# ring-modulator-v2_0.net
KiCad netlist of a schematic drawn in EAGLE
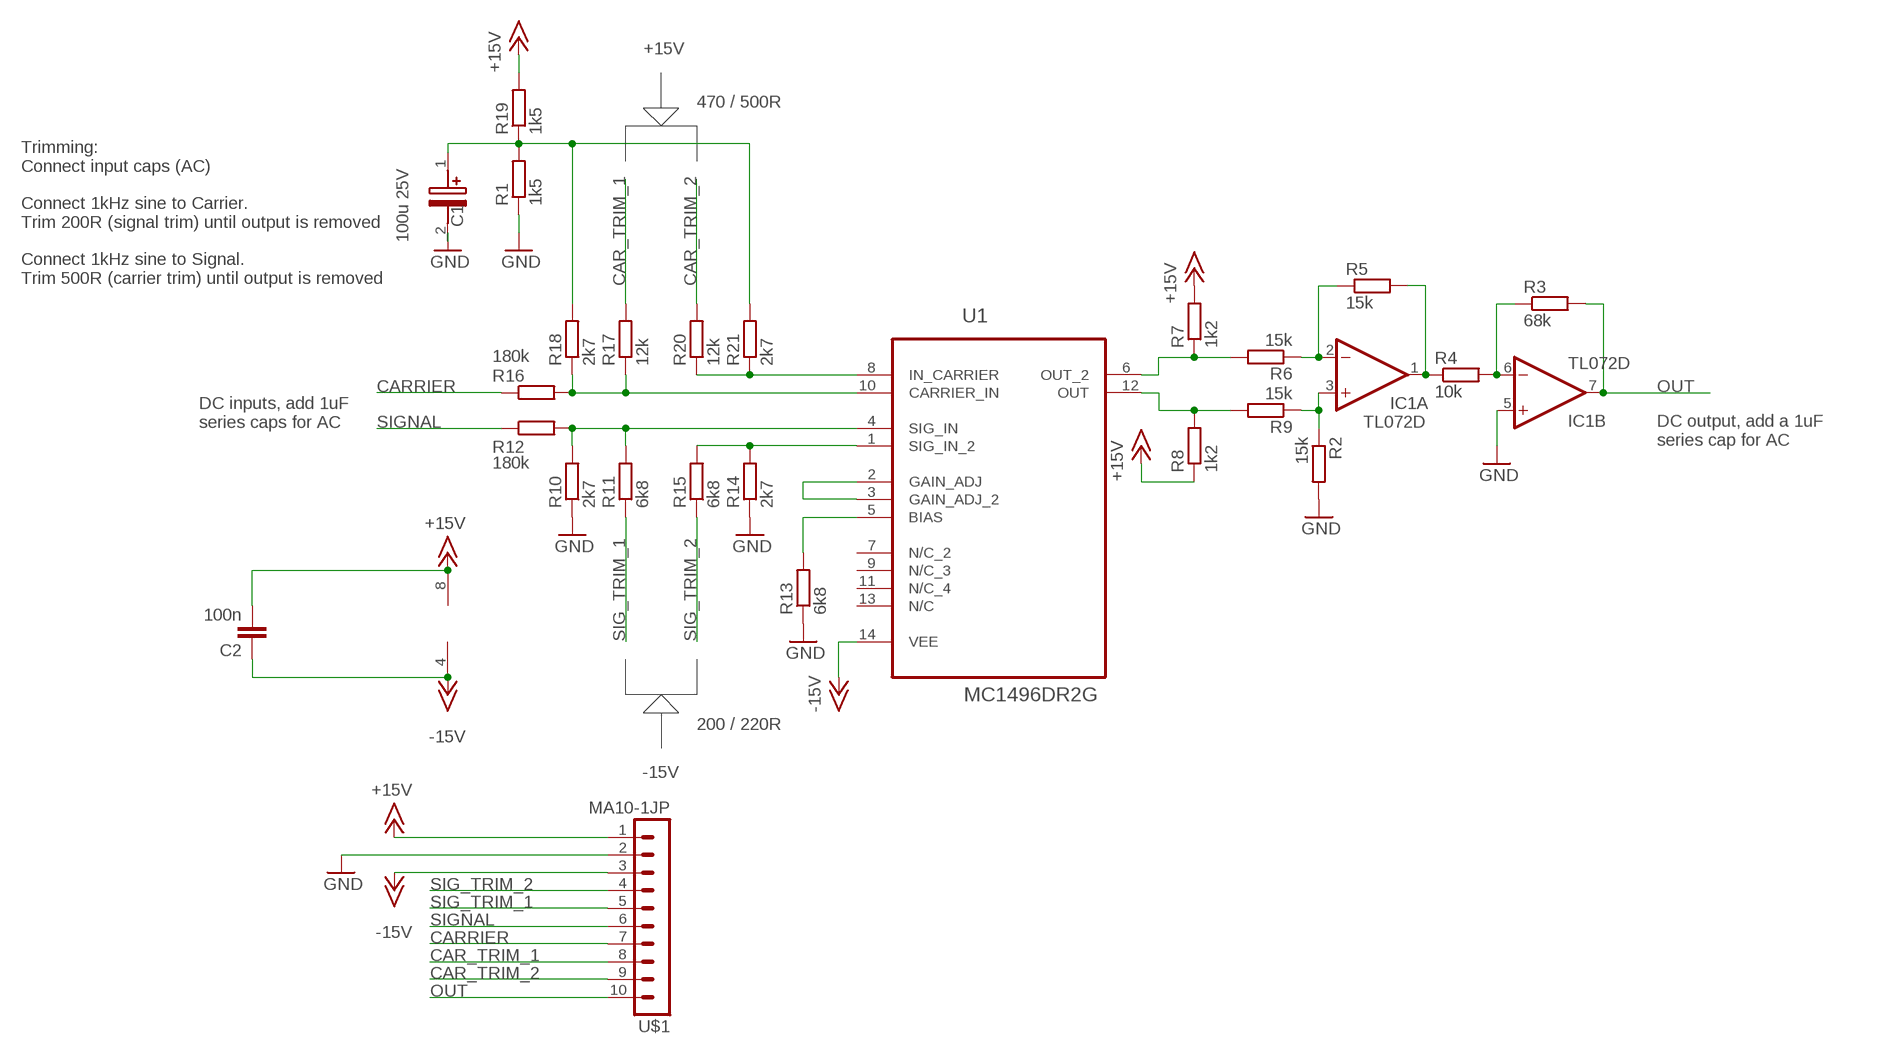
[diagram p0: schematic, sheet 1]

(export (version "E")
  (design (tool "Eeschema 10.0.6"))
  (components
    (comp (ref "C1")
      (value "100u 25V")
      (footprint "eagle-import:CAPAE660X610N")
      (fields
        (field (name "MANUFACTURER_PART_NUMBER") "VZL101M1CTR-0606")
        (field (name "MOUSER_PART_NUMBER") "140-VZL101M1CTR-0606")
      )
      (libsource (lib "eagle-import") (part "VZL101M1CTR-0606"))
    )
    (comp (ref "C2")
      (value "100n")
      (footprint "eagle-import:C0603")
      (libsource (lib "eagle-import") (part "C-EUC0603"))
    )
    (comp (ref "IC1")
      (value "TL072D")
      (footprint "eagle-import:SO08J")
      (libsource (lib "eagle-import") (part "TL072D"))
    )
    (comp (ref "R1")
      (value "1k5")
      (footprint "eagle-import:R0805")
      (libsource (lib "eagle-import") (part "R-EU_R0805"))
    )
    (comp (ref "R2")
      (value "15k")
      (footprint "eagle-import:R0805")
      (libsource (lib "eagle-import") (part "R-EU_R0805"))
    )
    (comp (ref "R3")
      (value "68k")
      (footprint "eagle-import:R0805")
      (libsource (lib "eagle-import") (part "R-EU_R0805"))
    )
    (comp (ref "R4")
      (value "10k")
      (footprint "eagle-import:R0805")
      (libsource (lib "eagle-import") (part "R-EU_R0805"))
    )
    (comp (ref "R5")
      (value "15k")
      (footprint "eagle-import:R0805")
      (libsource (lib "eagle-import") (part "R-EU_R0805"))
    )
    (comp (ref "R6")
      (value "15k")
      (footprint "eagle-import:R0805")
      (libsource (lib "eagle-import") (part "R-EU_R0805"))
    )
    (comp (ref "R7")
      (value "1k2")
      (footprint "eagle-import:R0805")
      (libsource (lib "eagle-import") (part "R-EU_R0805"))
    )
    (comp (ref "R8")
      (value "1k2")
      (footprint "eagle-import:R0805")
      (libsource (lib "eagle-import") (part "R-EU_R0805"))
    )
    (comp (ref "R9")
      (value "15k")
      (footprint "eagle-import:R0805")
      (libsource (lib "eagle-import") (part "R-EU_R0805"))
    )
    (comp (ref "R10")
      (value "2k7")
      (footprint "eagle-import:R0805")
      (libsource (lib "eagle-import") (part "R-EU_R0805"))
    )
    (comp (ref "R11")
      (value "6k8")
      (footprint "eagle-import:R0805")
      (libsource (lib "eagle-import") (part "R-EU_R0805"))
    )
    (comp (ref "R12")
      (value "180k")
      (footprint "eagle-import:R0805")
      (libsource (lib "eagle-import") (part "R-EU_R0805"))
    )
    (comp (ref "R13")
      (value "6k8")
      (footprint "eagle-import:R0805")
      (libsource (lib "eagle-import") (part "R-EU_R0805"))
    )
    (comp (ref "R14")
      (value "2k7")
      (footprint "eagle-import:R0805")
      (libsource (lib "eagle-import") (part "R-EU_R0805"))
    )
    (comp (ref "R15")
      (value "6k8")
      (footprint "eagle-import:R0805")
      (libsource (lib "eagle-import") (part "R-EU_R0805"))
    )
    (comp (ref "R16")
      (value "180k")
      (footprint "eagle-import:R0805")
      (libsource (lib "eagle-import") (part "R-EU_R0805"))
    )
    (comp (ref "R17")
      (value "12k")
      (footprint "eagle-import:R0805")
      (libsource (lib "eagle-import") (part "R-EU_R0805"))
    )
    (comp (ref "R18")
      (value "2k7")
      (footprint "eagle-import:R0805")
      (libsource (lib "eagle-import") (part "R-EU_R0805"))
    )
    (comp (ref "R19")
      (value "1k5")
      (footprint "eagle-import:R0805")
      (libsource (lib "eagle-import") (part "R-EU_R0805"))
    )
    (comp (ref "R20")
      (value "12k")
      (footprint "eagle-import:R0805")
      (libsource (lib "eagle-import") (part "R-EU_R0805"))
    )
    (comp (ref "R21")
      (value "2k7")
      (footprint "eagle-import:R0805")
      (libsource (lib "eagle-import") (part "R-EU_R0805"))
    )
    (comp (ref "U$1")
      (value "MA10-1JP")
      (footprint "eagle-import:SIP-PIN10-1J")
      (libsource (lib "eagle-import") (part "MA10-1JP"))
    )
    (comp (ref "U1")
      (value "MC1496DR2G")
      (footprint "eagle-import:SOIC127P600X175-14N")
      (libsource (lib "eagle-import") (part "MC1496DR2G"))
    )
  )
  (nets
    (net (code "1") (name "+15V") (class "Default")
      (node (ref "C2") (pin "2") (pinfunction "2_2") (pintype "passive"))
      (node (ref "IC1") (pin "8") (pinfunction "V+_8") (pintype "power_in"))
      (node (ref "R19") (pin "2") (pinfunction "2_2") (pintype "passive"))
      (node (ref "R7") (pin "2") (pinfunction "2_2") (pintype "passive"))
      (node (ref "R8") (pin "1") (pinfunction "1_1") (pintype "passive"))
      (node (ref "U$1") (pin "1") (pinfunction "1_1") (pintype "passive"))
    )
    (net (code "2") (name "-15V") (class "Default")
      (node (ref "C2") (pin "1") (pinfunction "1_1") (pintype "passive"))
      (node (ref "IC1") (pin "4") (pinfunction "V-_4") (pintype "power_in"))
      (node (ref "U$1") (pin "3") (pinfunction "3_3") (pintype "passive"))
      (node (ref "U1") (pin "14") (pinfunction "VEE_14") (pintype "passive"))
    )
    (net (code "3") (name "/CARRIER") (class "Default")
      (node (ref "R16") (pin "1") (pinfunction "1_1") (pintype "passive"))
      (node (ref "U$1") (pin "7") (pinfunction "7_7") (pintype "passive"))
    )
    (net (code "4") (name "/CAR_TRIM_1") (class "Default")
      (node (ref "R17") (pin "2") (pinfunction "2_2") (pintype "passive"))
      (node (ref "U$1") (pin "8") (pinfunction "8_8") (pintype "passive"))
    )
    (net (code "5") (name "/CAR_TRIM_2") (class "Default")
      (node (ref "R20") (pin "2") (pinfunction "2_2") (pintype "passive"))
      (node (ref "U$1") (pin "9") (pinfunction "9_9") (pintype "passive"))
    )
    (net (code "6") (name "/OUT") (class "Default")
      (node (ref "IC1") (pin "7") (pinfunction "OUT_7") (pintype "output"))
      (node (ref "R3") (pin "2") (pinfunction "2_2") (pintype "passive"))
      (node (ref "U$1") (pin "10") (pinfunction "10_10") (pintype "passive"))
    )
    (net (code "7") (name "/SIGNAL") (class "Default")
      (node (ref "R12") (pin "1") (pinfunction "1_1") (pintype "passive"))
      (node (ref "U$1") (pin "6") (pinfunction "6_6") (pintype "passive"))
    )
    (net (code "8") (name "/SIG_TRIM_1") (class "Default")
      (node (ref "R11") (pin "1") (pinfunction "1_1") (pintype "passive"))
      (node (ref "U$1") (pin "5") (pinfunction "5_5") (pintype "passive"))
    )
    (net (code "9") (name "/SIG_TRIM_2") (class "Default")
      (node (ref "R15") (pin "1") (pinfunction "1_1") (pintype "passive"))
      (node (ref "U$1") (pin "4") (pinfunction "4_4") (pintype "passive"))
    )
    (net (code "10") (name "GND") (class "Default")
      (node (ref "C1") (pin "2") (pinfunction "-_2") (pintype "bidirectional"))
      (node (ref "IC1") (pin "5") (pinfunction "+IN_5") (pintype "input"))
      (node (ref "R1") (pin "1") (pinfunction "1_1") (pintype "passive"))
      (node (ref "R10") (pin "1") (pinfunction "1_1") (pintype "passive"))
      (node (ref "R13") (pin "1") (pinfunction "1_1") (pintype "passive"))
      (node (ref "R14") (pin "1") (pinfunction "1_1") (pintype "passive"))
      (node (ref "R2") (pin "2") (pinfunction "2_2") (pintype "passive"))
      (node (ref "U$1") (pin "2") (pinfunction "2_2") (pintype "passive"))
    )
    (net (code "11") (name "Net-(C1-+)") (class "Default")
      (node (ref "C1") (pin "1") (pinfunction "+_1") (pintype "bidirectional"))
      (node (ref "R1") (pin "2") (pinfunction "2_2") (pintype "passive"))
      (node (ref "R18") (pin "2") (pinfunction "2_2") (pintype "passive"))
      (node (ref "R19") (pin "1") (pinfunction "1_1") (pintype "passive"))
      (node (ref "R21") (pin "2") (pinfunction "2_2") (pintype "passive"))
    )
    (net (code "12") (name "Net-(IC1A-+IN)") (class "Default")
      (node (ref "IC1") (pin "3") (pinfunction "+IN_3") (pintype "input"))
      (node (ref "R2") (pin "1") (pinfunction "1_1") (pintype "passive"))
      (node (ref "R9") (pin "1") (pinfunction "1_1") (pintype "passive"))
    )
    (net (code "13") (name "Net-(IC1A--IN)") (class "Default")
      (node (ref "IC1") (pin "2") (pinfunction "-IN_2") (pintype "input"))
      (node (ref "R5") (pin "1") (pinfunction "1_1") (pintype "passive"))
      (node (ref "R6") (pin "1") (pinfunction "1_1") (pintype "passive"))
    )
    (net (code "14") (name "Net-(IC1A-OUT)") (class "Default")
      (node (ref "IC1") (pin "1") (pinfunction "OUT_1") (pintype "output"))
      (node (ref "R4") (pin "1") (pinfunction "1_1") (pintype "passive"))
      (node (ref "R5") (pin "2") (pinfunction "2_2") (pintype "passive"))
    )
    (net (code "15") (name "Net-(IC1B--IN)") (class "Default")
      (node (ref "IC1") (pin "6") (pinfunction "-IN_6") (pintype "input"))
      (node (ref "R3") (pin "1") (pinfunction "1_1") (pintype "passive"))
      (node (ref "R4") (pin "2") (pinfunction "2_2") (pintype "passive"))
    )
    (net (code "16") (name "Net-(U1-BIAS)") (class "Default")
      (node (ref "R13") (pin "2") (pinfunction "2_2") (pintype "passive"))
      (node (ref "U1") (pin "5") (pinfunction "BIAS_5") (pintype "input"))
    )
    (net (code "17") (name "Net-(U1-CARRIER_IN)") (class "Default")
      (node (ref "R16") (pin "2") (pinfunction "2_2") (pintype "passive"))
      (node (ref "R17") (pin "1") (pinfunction "1_1") (pintype "passive"))
      (node (ref "R18") (pin "1") (pinfunction "1_1") (pintype "passive"))
      (node (ref "U1") (pin "10") (pinfunction "CARRIER_IN_10") (pintype "power_in"))
    )
    (net (code "18") (name "Net-(U1-GAIN_ADJ)") (class "Default")
      (node (ref "U1") (pin "2") (pinfunction "GAIN_ADJ_2") (pintype "input"))
      (node (ref "U1") (pin "3") (pinfunction "GAIN_ADJ_2_3") (pintype "input"))
    )
    (net (code "19") (name "Net-(U1-IN_CARRIER)") (class "Default")
      (node (ref "R20") (pin "1") (pinfunction "1_1") (pintype "passive"))
      (node (ref "R21") (pin "1") (pinfunction "1_1") (pintype "passive"))
      (node (ref "U1") (pin "8") (pinfunction "IN_CARRIER_8") (pintype "power_in"))
    )
    (net (code "20") (name "Net-(U1-OUT)") (class "Default")
      (node (ref "R8") (pin "2") (pinfunction "2_2") (pintype "passive"))
      (node (ref "R9") (pin "2") (pinfunction "2_2") (pintype "passive"))
      (node (ref "U1") (pin "12") (pinfunction "OUT_12") (pintype "output"))
    )
    (net (code "21") (name "Net-(U1-OUT_2)") (class "Default")
      (node (ref "R6") (pin "2") (pinfunction "2_2") (pintype "passive"))
      (node (ref "R7") (pin "1") (pinfunction "1_1") (pintype "passive"))
      (node (ref "U1") (pin "6") (pinfunction "OUT_2_6") (pintype "output"))
    )
    (net (code "22") (name "Net-(U1-SIG_IN)") (class "Default")
      (node (ref "R10") (pin "2") (pinfunction "2_2") (pintype "passive"))
      (node (ref "R11") (pin "2") (pinfunction "2_2") (pintype "passive"))
      (node (ref "R12") (pin "2") (pinfunction "2_2") (pintype "passive"))
      (node (ref "U1") (pin "4") (pinfunction "SIG_IN_4") (pintype "input"))
    )
    (net (code "23") (name "Net-(U1-SIG_IN_2)") (class "Default")
      (node (ref "R14") (pin "2") (pinfunction "2_2") (pintype "passive"))
      (node (ref "R15") (pin "2") (pinfunction "2_2") (pintype "passive"))
      (node (ref "U1") (pin "1") (pinfunction "SIG_IN_2_1") (pintype "input"))
    )
    (net (code "24") (name "unconnected-(U1-N{slash}C-Pad13)") (class "Default")
      (node (ref "U1") (pin "13") (pinfunction "N/C_13") (pintype "no_connect"))
    )
    (net (code "25") (name "unconnected-(U1-N{slash}C_2-Pad7)") (class "Default")
      (node (ref "U1") (pin "7") (pinfunction "N/C_2_7") (pintype "no_connect"))
    )
    (net (code "26") (name "unconnected-(U1-N{slash}C_3-Pad9)") (class "Default")
      (node (ref "U1") (pin "9") (pinfunction "N/C_3_9") (pintype "no_connect"))
    )
    (net (code "27") (name "unconnected-(U1-N{slash}C_4-Pad11)") (class "Default")
      (node (ref "U1") (pin "11") (pinfunction "N/C_4_11") (pintype "no_connect"))
    )
  )
)
